# femto.net
KiCad netlist of a schematic drawn in EAGLE
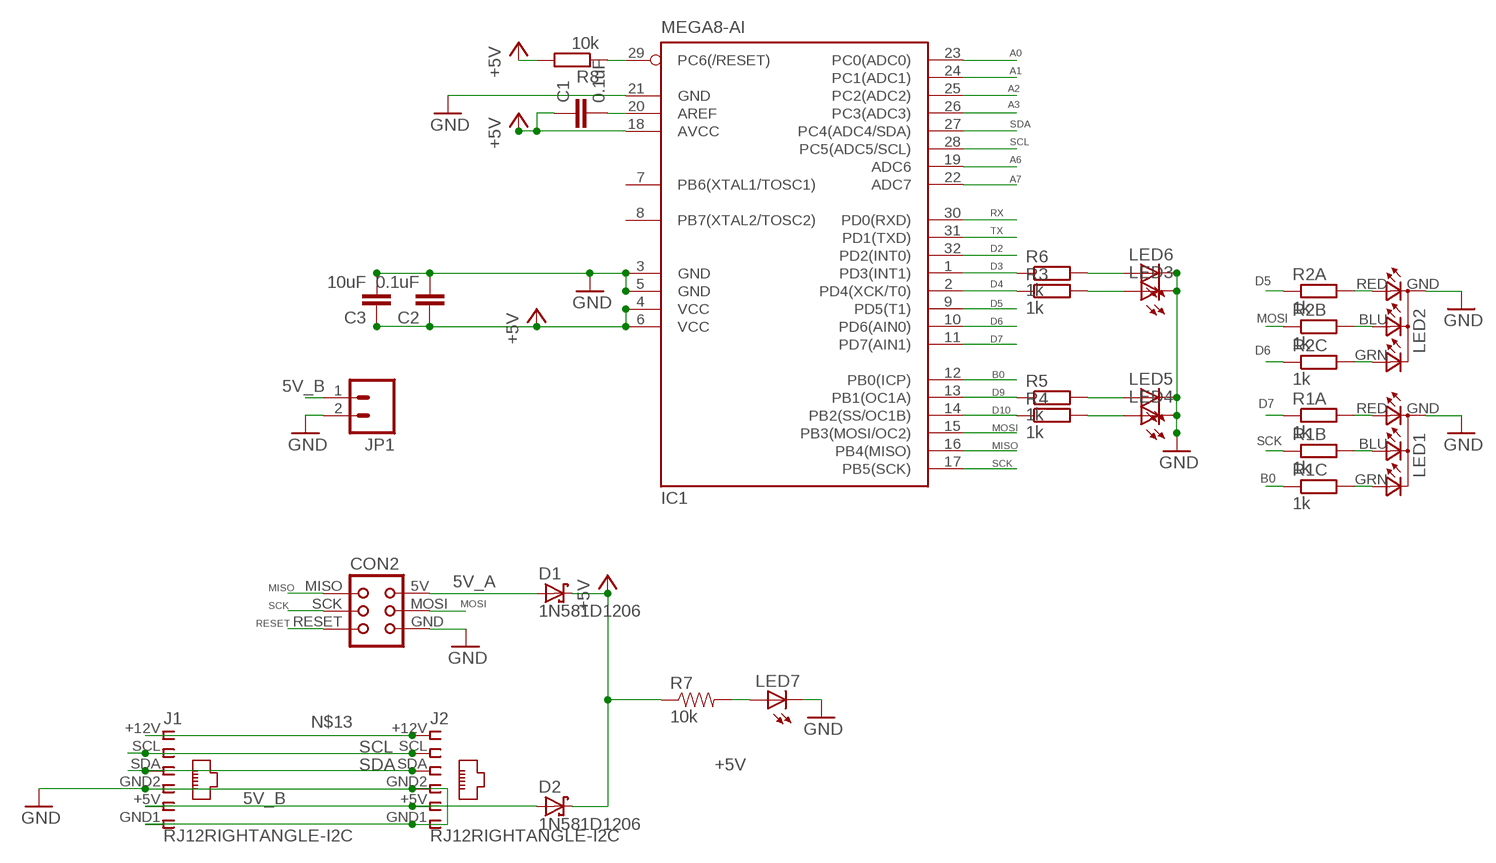
[diagram p0: schematic, sheet 1]

(export (version "E")
  (design (tool "Eeschema 10.0.6"))
  (components
    (comp (ref "C1")
      (value "0.1uF")
      (footprint "eagle-import:C1206")
      (libsource (lib "eagle-import") (part "C-EUC1206"))
    )
    (comp (ref "C2")
      (value "0.1uF")
      (footprint "eagle-import:C1206")
      (libsource (lib "eagle-import") (part "C-EUC1206"))
    )
    (comp (ref "C3")
      (value "10uF")
      (footprint "eagle-import:C1206")
      (libsource (lib "eagle-import") (part "C-EUC1206"))
    )
    (comp (ref "CON2")
      (value "TINYISPTAG")
      (footprint "eagle-import:TC2030-MCP")
      (libsource (lib "eagle-import") (part "TINYISPTAG"))
    )
    (comp (ref "D1")
      (value "1N581D1206")
      (footprint "eagle-import:LED-1206")
      (libsource (lib "eagle-import") (part "1N581D1206"))
    )
    (comp (ref "D2")
      (value "1N581D1206")
      (footprint "eagle-import:LED-1206")
      (libsource (lib "eagle-import") (part "1N581D1206"))
    )
    (comp (ref "IC1")
      (value "MEGA8-AI")
      (footprint "eagle-import:TQFP32-08")
      (fields (field (name "MPN") "ATMEGA8-16AU"))
      (libsource (lib "eagle-import") (part "MEGA8-AI"))
    )
    (comp (ref "J1")
      (value "RJ12RIGHTANGLE-I2C")
      (footprint "eagle-import:RJ12-RIGHTANGLE-I2C")
      (libsource (lib "eagle-import") (part "RJ12RIGHTANGLE-I2C"))
    )
    (comp (ref "J2")
      (value "RJ12RIGHTANGLE-I2C")
      (footprint "eagle-import:RJ12-RIGHTANGLE-I2C")
      (libsource (lib "eagle-import") (part "RJ12RIGHTANGLE-I2C"))
    )
    (comp (ref "JP1")
      (value "M023.5MM")
      (footprint "eagle-import:SCREWTERMINAL-3.5MM-2")
      (libsource (lib "eagle-import") (part "M023.5MM"))
    )
    (comp (ref "LED1")
      (value "RGB-COMMON-CATHODE")
      (footprint "eagle-import:LED-TRICOLOR-THROUGHHOLE")
      (libsource (lib "eagle-import") (part "RGB-COMMON-CATHODE"))
    )
    (comp (ref "LED2")
      (value "RGB-COMMON-CATHODE")
      (footprint "eagle-import:LED-TRICOLOR-THROUGHHOLE")
      (libsource (lib "eagle-import") (part "RGB-COMMON-CATHODE"))
    )
    (comp (ref "LED3")
      (value "LED3MM")
      (footprint "eagle-import:LED3MM")
      (libsource (lib "eagle-import") (part "lpatiny_LED3MM"))
    )
    (comp (ref "LED4")
      (value "LED3MM")
      (footprint "eagle-import:LED3MM")
      (libsource (lib "eagle-import") (part "lpatiny_LED3MM"))
    )
    (comp (ref "LED5")
      (value "LED3MM")
      (footprint "eagle-import:LED3MM")
      (libsource (lib "eagle-import") (part "lpatiny_LED3MM"))
    )
    (comp (ref "LED6")
      (value "LED3MM")
      (footprint "eagle-import:LED3MM")
      (libsource (lib "eagle-import") (part "lpatiny_LED3MM"))
    )
    (comp (ref "LED7")
      (value "LEDCHIP-LED0603")
      (footprint "eagle-import:CHIP-LED0603")
      (libsource (lib "eagle-import") (part "LEDCHIP-LED0603"))
    )
    (comp (ref "R1A")
      (value "1k")
      (footprint "eagle-import:M1206")
      (libsource (lib "eagle-import") (part "R-EU_M1206"))
    )
    (comp (ref "R1B")
      (value "1k")
      (footprint "eagle-import:M1206")
      (libsource (lib "eagle-import") (part "R-EU_M1206"))
    )
    (comp (ref "R1C")
      (value "1k")
      (footprint "eagle-import:M1206")
      (libsource (lib "eagle-import") (part "R-EU_M1206"))
    )
    (comp (ref "R2A")
      (value "1k")
      (footprint "eagle-import:M1206")
      (libsource (lib "eagle-import") (part "R-EU_M1206"))
    )
    (comp (ref "R2B")
      (value "1k")
      (footprint "eagle-import:M1206")
      (libsource (lib "eagle-import") (part "R-EU_M1206"))
    )
    (comp (ref "R2C")
      (value "1k")
      (footprint "eagle-import:M1206")
      (libsource (lib "eagle-import") (part "R-EU_M1206"))
    )
    (comp (ref "R3")
      (value "1k")
      (footprint "eagle-import:M1206")
      (libsource (lib "eagle-import") (part "R-EU_M1206"))
    )
    (comp (ref "R4")
      (value "1k")
      (footprint "eagle-import:M1206")
      (libsource (lib "eagle-import") (part "R-EU_M1206"))
    )
    (comp (ref "R5")
      (value "1k")
      (footprint "eagle-import:M1206")
      (libsource (lib "eagle-import") (part "R-EU_M1206"))
    )
    (comp (ref "R6")
      (value "1k")
      (footprint "eagle-import:M1206")
      (libsource (lib "eagle-import") (part "R-EU_M1206"))
    )
    (comp (ref "R7")
      (value "10k")
      (footprint "eagle-import:0603-RES")
      (libsource (lib "eagle-import") (part "RESISTOR0603-RES"))
    )
    (comp (ref "R8")
      (value "10k")
      (footprint "eagle-import:M1206")
      (libsource (lib "eagle-import") (part "R-EU_M1206"))
    )
  )
  (nets
    (net (code "1") (name "+5V") (class "Default")
      (node (ref "C1") (pin "1") (pinfunction "1_1") (pintype "passive"))
      (node (ref "C2") (pin "1") (pinfunction "1_1") (pintype "passive"))
      (node (ref "C3") (pin "1") (pinfunction "1_1") (pintype "passive"))
      (node (ref "D1") (pin "C") (pinfunction "C_C") (pintype "passive"))
      (node (ref "D2") (pin "C") (pinfunction "C_C") (pintype "passive"))
      (node (ref "IC1") (pin "18") (pinfunction "AVCC_18") (pintype "power_in"))
      (node (ref "IC1") (pin "4") (pinfunction "VCC_4") (pintype "power_in"))
      (node (ref "IC1") (pin "6") (pinfunction "VCC_6") (pintype "power_in"))
      (node (ref "R7") (pin "1") (pinfunction "1_1") (pintype "passive"))
      (node (ref "R8") (pin "2") (pinfunction "2_2") (pintype "passive"))
    )
    (net (code "2") (name "/5V_A") (class "Default")
      (node (ref "CON2") (pin "5V") (pinfunction "VCC_5V") (pintype "passive"))
      (node (ref "D1") (pin "A") (pinfunction "A_A") (pintype "passive"))
    )
    (net (code "3") (name "/5V_B") (class "Default")
      (node (ref "D2") (pin "A") (pinfunction "A_A") (pintype "passive"))
      (node (ref "J1") (pin "+5V") (pinfunction "5_+5V") (pintype "bidirectional"))
      (node (ref "J2") (pin "+5V") (pinfunction "5_+5V") (pintype "bidirectional"))
      (node (ref "JP1") (pin "1") (pinfunction "1_1") (pintype "passive"))
    )
    (net (code "4") (name "/A0") (class "Default")
      (node (ref "IC1") (pin "23") (pinfunction "PC0(ADC0)_23") (pintype "bidirectional"))
    )
    (net (code "5") (name "/A1") (class "Default")
      (node (ref "IC1") (pin "24") (pinfunction "PC1(ADC1)_24") (pintype "bidirectional"))
    )
    (net (code "6") (name "/A2") (class "Default")
      (node (ref "IC1") (pin "25") (pinfunction "PC2(ADC2)_25") (pintype "bidirectional"))
    )
    (net (code "7") (name "/A3") (class "Default")
      (node (ref "IC1") (pin "26") (pinfunction "PC3(ADC3)_26") (pintype "bidirectional"))
    )
    (net (code "8") (name "/A6") (class "Default")
      (node (ref "IC1") (pin "19") (pinfunction "ADC6_19") (pintype "bidirectional"))
    )
    (net (code "9") (name "/A7") (class "Default")
      (node (ref "IC1") (pin "22") (pinfunction "ADC7_22") (pintype "bidirectional"))
    )
    (net (code "10") (name "/B0") (class "Default")
      (node (ref "IC1") (pin "12") (pinfunction "PB0(ICP)_12") (pintype "bidirectional"))
      (node (ref "R1C") (pin "1") (pinfunction "1_1") (pintype "passive"))
    )
    (net (code "11") (name "/D2") (class "Default")
      (node (ref "IC1") (pin "32") (pinfunction "PD2(INT0)_32") (pintype "bidirectional"))
    )
    (net (code "12") (name "/D3") (class "Default")
      (node (ref "IC1") (pin "1") (pinfunction "PD3(INT1)_1") (pintype "bidirectional"))
      (node (ref "R6") (pin "1") (pinfunction "1_1") (pintype "passive"))
    )
    (net (code "13") (name "/D4") (class "Default")
      (node (ref "IC1") (pin "2") (pinfunction "PD4(XCK/T0)_2") (pintype "bidirectional"))
      (node (ref "R3") (pin "1") (pinfunction "1_1") (pintype "passive"))
    )
    (net (code "14") (name "/D5") (class "Default")
      (node (ref "IC1") (pin "9") (pinfunction "PD5(T1)_9") (pintype "bidirectional"))
      (node (ref "R2A") (pin "1") (pinfunction "1_1") (pintype "passive"))
    )
    (net (code "15") (name "/D6") (class "Default")
      (node (ref "IC1") (pin "10") (pinfunction "PD6(AIN0)_10") (pintype "bidirectional"))
      (node (ref "R2C") (pin "1") (pinfunction "1_1") (pintype "passive"))
    )
    (net (code "16") (name "/D7") (class "Default")
      (node (ref "IC1") (pin "11") (pinfunction "PD7(AIN1)_11") (pintype "bidirectional"))
      (node (ref "R1A") (pin "1") (pinfunction "1_1") (pintype "passive"))
    )
    (net (code "17") (name "/D9") (class "Default")
      (node (ref "IC1") (pin "13") (pinfunction "PB1(OC1A)_13") (pintype "bidirectional"))
      (node (ref "R5") (pin "1") (pinfunction "1_1") (pintype "passive"))
    )
    (net (code "18") (name "/D10") (class "Default")
      (node (ref "IC1") (pin "14") (pinfunction "PB2(SS/OC1B)_14") (pintype "bidirectional"))
      (node (ref "R4") (pin "1") (pinfunction "1_1") (pintype "passive"))
    )
    (net (code "19") (name "/MISO") (class "Default")
      (node (ref "CON2") (pin "MISO") (pinfunction "MISO_MISO") (pintype "passive"))
      (node (ref "IC1") (pin "16") (pinfunction "PB4(MISO)_16") (pintype "bidirectional"))
    )
    (net (code "20") (name "/MOSI") (class "Default")
      (node (ref "CON2") (pin "MOSI") (pinfunction "MOSI_MOSI") (pintype "passive"))
      (node (ref "IC1") (pin "15") (pinfunction "PB3(MOSI/OC2)_15") (pintype "bidirectional"))
      (node (ref "R2B") (pin "1") (pinfunction "1_1") (pintype "passive"))
    )
    (net (code "21") (name "/N$13") (class "Default")
      (node (ref "J1") (pin "+12V") (pinfunction "1_+12V") (pintype "bidirectional"))
      (node (ref "J2") (pin "+12V") (pinfunction "1_+12V") (pintype "bidirectional"))
    )
    (net (code "22") (name "/RESET") (class "Default")
      (node (ref "CON2") (pin "RESET") (pinfunction "RESET_RESET") (pintype "passive"))
      (node (ref "IC1") (pin "29") (pinfunction "PC6(/RESET)_29") (pintype "bidirectional"))
      (node (ref "R8") (pin "1") (pinfunction "1_1") (pintype "passive"))
    )
    (net (code "23") (name "/RX") (class "Default")
      (node (ref "IC1") (pin "30") (pinfunction "PD0(RXD)_30") (pintype "bidirectional"))
    )
    (net (code "24") (name "/SCK") (class "Default")
      (node (ref "CON2") (pin "SCK") (pinfunction "SCK_SCK") (pintype "passive"))
      (node (ref "IC1") (pin "17") (pinfunction "PB5(SCK)_17") (pintype "bidirectional"))
      (node (ref "R1B") (pin "1") (pinfunction "1_1") (pintype "passive"))
    )
    (net (code "25") (name "/SCL") (class "Default")
      (node (ref "IC1") (pin "28") (pinfunction "PC5(ADC5/SCL)_28") (pintype "bidirectional"))
      (node (ref "J1") (pin "SCL") (pinfunction "2_SCL") (pintype "bidirectional"))
      (node (ref "J2") (pin "SCL") (pinfunction "2_SCL") (pintype "bidirectional"))
    )
    (net (code "26") (name "/SDA") (class "Default")
      (node (ref "IC1") (pin "27") (pinfunction "PC4(ADC4/SDA)_27") (pintype "bidirectional"))
      (node (ref "J1") (pin "SDA") (pinfunction "3_SDA") (pintype "bidirectional"))
      (node (ref "J2") (pin "SDA") (pinfunction "3_SDA") (pintype "bidirectional"))
    )
    (net (code "27") (name "/TX") (class "Default")
      (node (ref "IC1") (pin "31") (pinfunction "PD1(TXD)_31") (pintype "bidirectional"))
    )
    (net (code "28") (name "GND") (class "Default")
      (node (ref "C2") (pin "2") (pinfunction "2_2") (pintype "passive"))
      (node (ref "C3") (pin "2") (pinfunction "2_2") (pintype "passive"))
      (node (ref "CON2") (pin "GND") (pinfunction "GND_GND") (pintype "passive"))
      (node (ref "IC1") (pin "21") (pinfunction "GND_21") (pintype "power_in"))
      (node (ref "IC1") (pin "3") (pinfunction "GND_3") (pintype "power_in"))
      (node (ref "IC1") (pin "5") (pinfunction "GND_5") (pintype "power_in"))
      (node (ref "J1") (pin "GND1") (pinfunction "6_GND1") (pintype "bidirectional"))
      (node (ref "J1") (pin "GND2") (pinfunction "4_GND2") (pintype "bidirectional"))
      (node (ref "J2") (pin "GND1") (pinfunction "6_GND1") (pintype "bidirectional"))
      (node (ref "J2") (pin "GND2") (pinfunction "4_GND2") (pintype "bidirectional"))
      (node (ref "JP1") (pin "2") (pinfunction "2_2") (pintype "passive"))
      (node (ref "LED1") (pin "GND") (pinfunction "A2_GND") (pintype "passive"))
      (node (ref "LED2") (pin "GND") (pinfunction "A2_GND") (pintype "passive"))
      (node (ref "LED3") (pin "K") (pinfunction "C_K") (pintype "passive"))
      (node (ref "LED4") (pin "K") (pinfunction "C_K") (pintype "passive"))
      (node (ref "LED5") (pin "K") (pinfunction "C_K") (pintype "passive"))
      (node (ref "LED6") (pin "K") (pinfunction "C_K") (pintype "passive"))
      (node (ref "LED7") (pin "C") (pinfunction "C_C") (pintype "passive"))
    )
    (net (code "29") (name "Net-(IC1-AREF)") (class "Default")
      (node (ref "C1") (pin "2") (pinfunction "2_2") (pintype "passive"))
      (node (ref "IC1") (pin "20") (pinfunction "AREF_20") (pintype "passive"))
    )
    (net (code "30") (name "Net-(LED1-CBLUE)") (class "Default")
      (node (ref "LED1") (pin "BLU") (pinfunction "CBLUE_BLU") (pintype "passive"))
      (node (ref "R1B") (pin "2") (pinfunction "2_2") (pintype "passive"))
    )
    (net (code "31") (name "Net-(LED1-CGREEN)") (class "Default")
      (node (ref "LED1") (pin "GRN") (pinfunction "CGREEN_GRN") (pintype "passive"))
      (node (ref "R1C") (pin "2") (pinfunction "2_2") (pintype "passive"))
    )
    (net (code "32") (name "Net-(LED1-CRED)") (class "Default")
      (node (ref "LED1") (pin "RED") (pinfunction "CRED_RED") (pintype "passive"))
      (node (ref "R1A") (pin "2") (pinfunction "2_2") (pintype "passive"))
    )
    (net (code "33") (name "Net-(LED2-CBLUE)") (class "Default")
      (node (ref "LED2") (pin "BLU") (pinfunction "CBLUE_BLU") (pintype "passive"))
      (node (ref "R2B") (pin "2") (pinfunction "2_2") (pintype "passive"))
    )
    (net (code "34") (name "Net-(LED2-CGREEN)") (class "Default")
      (node (ref "LED2") (pin "GRN") (pinfunction "CGREEN_GRN") (pintype "passive"))
      (node (ref "R2C") (pin "2") (pinfunction "2_2") (pintype "passive"))
    )
    (net (code "35") (name "Net-(LED2-CRED)") (class "Default")
      (node (ref "LED2") (pin "RED") (pinfunction "CRED_RED") (pintype "passive"))
      (node (ref "R2A") (pin "2") (pinfunction "2_2") (pintype "passive"))
    )
    (net (code "36") (name "Net-(LED3-PadA)") (class "Default")
      (node (ref "LED3") (pin "A") (pinfunction "A_A") (pintype "passive"))
      (node (ref "R3") (pin "2") (pinfunction "2_2") (pintype "passive"))
    )
    (net (code "37") (name "Net-(LED4-PadA)") (class "Default")
      (node (ref "LED4") (pin "A") (pinfunction "A_A") (pintype "passive"))
      (node (ref "R4") (pin "2") (pinfunction "2_2") (pintype "passive"))
    )
    (net (code "38") (name "Net-(LED5-PadA)") (class "Default")
      (node (ref "LED5") (pin "A") (pinfunction "A_A") (pintype "passive"))
      (node (ref "R5") (pin "2") (pinfunction "2_2") (pintype "passive"))
    )
    (net (code "39") (name "Net-(LED6-PadA)") (class "Default")
      (node (ref "LED6") (pin "A") (pinfunction "A_A") (pintype "passive"))
      (node (ref "R6") (pin "2") (pinfunction "2_2") (pintype "passive"))
    )
    (net (code "40") (name "Net-(LED7-PadA)") (class "Default")
      (node (ref "LED7") (pin "A") (pinfunction "A_A") (pintype "passive"))
      (node (ref "R7") (pin "2") (pinfunction "2_2") (pintype "passive"))
    )
    (net (code "41") (name "unconnected-(IC1-PB6(XTAL1{slash}TOSC1)-Pad7)") (class "Default")
      (node (ref "IC1") (pin "7") (pinfunction "PB6(XTAL1/TOSC1)_7") (pintype "bidirectional"))
    )
    (net (code "42") (name "unconnected-(IC1-PB7(XTAL2{slash}TOSC2)-Pad8)") (class "Default")
      (node (ref "IC1") (pin "8") (pinfunction "PB7(XTAL2/TOSC2)_8") (pintype "bidirectional"))
    )
  )
)
